# MotorCellOne.net
KiCad netlist of a schematic drawn in Altium Designer
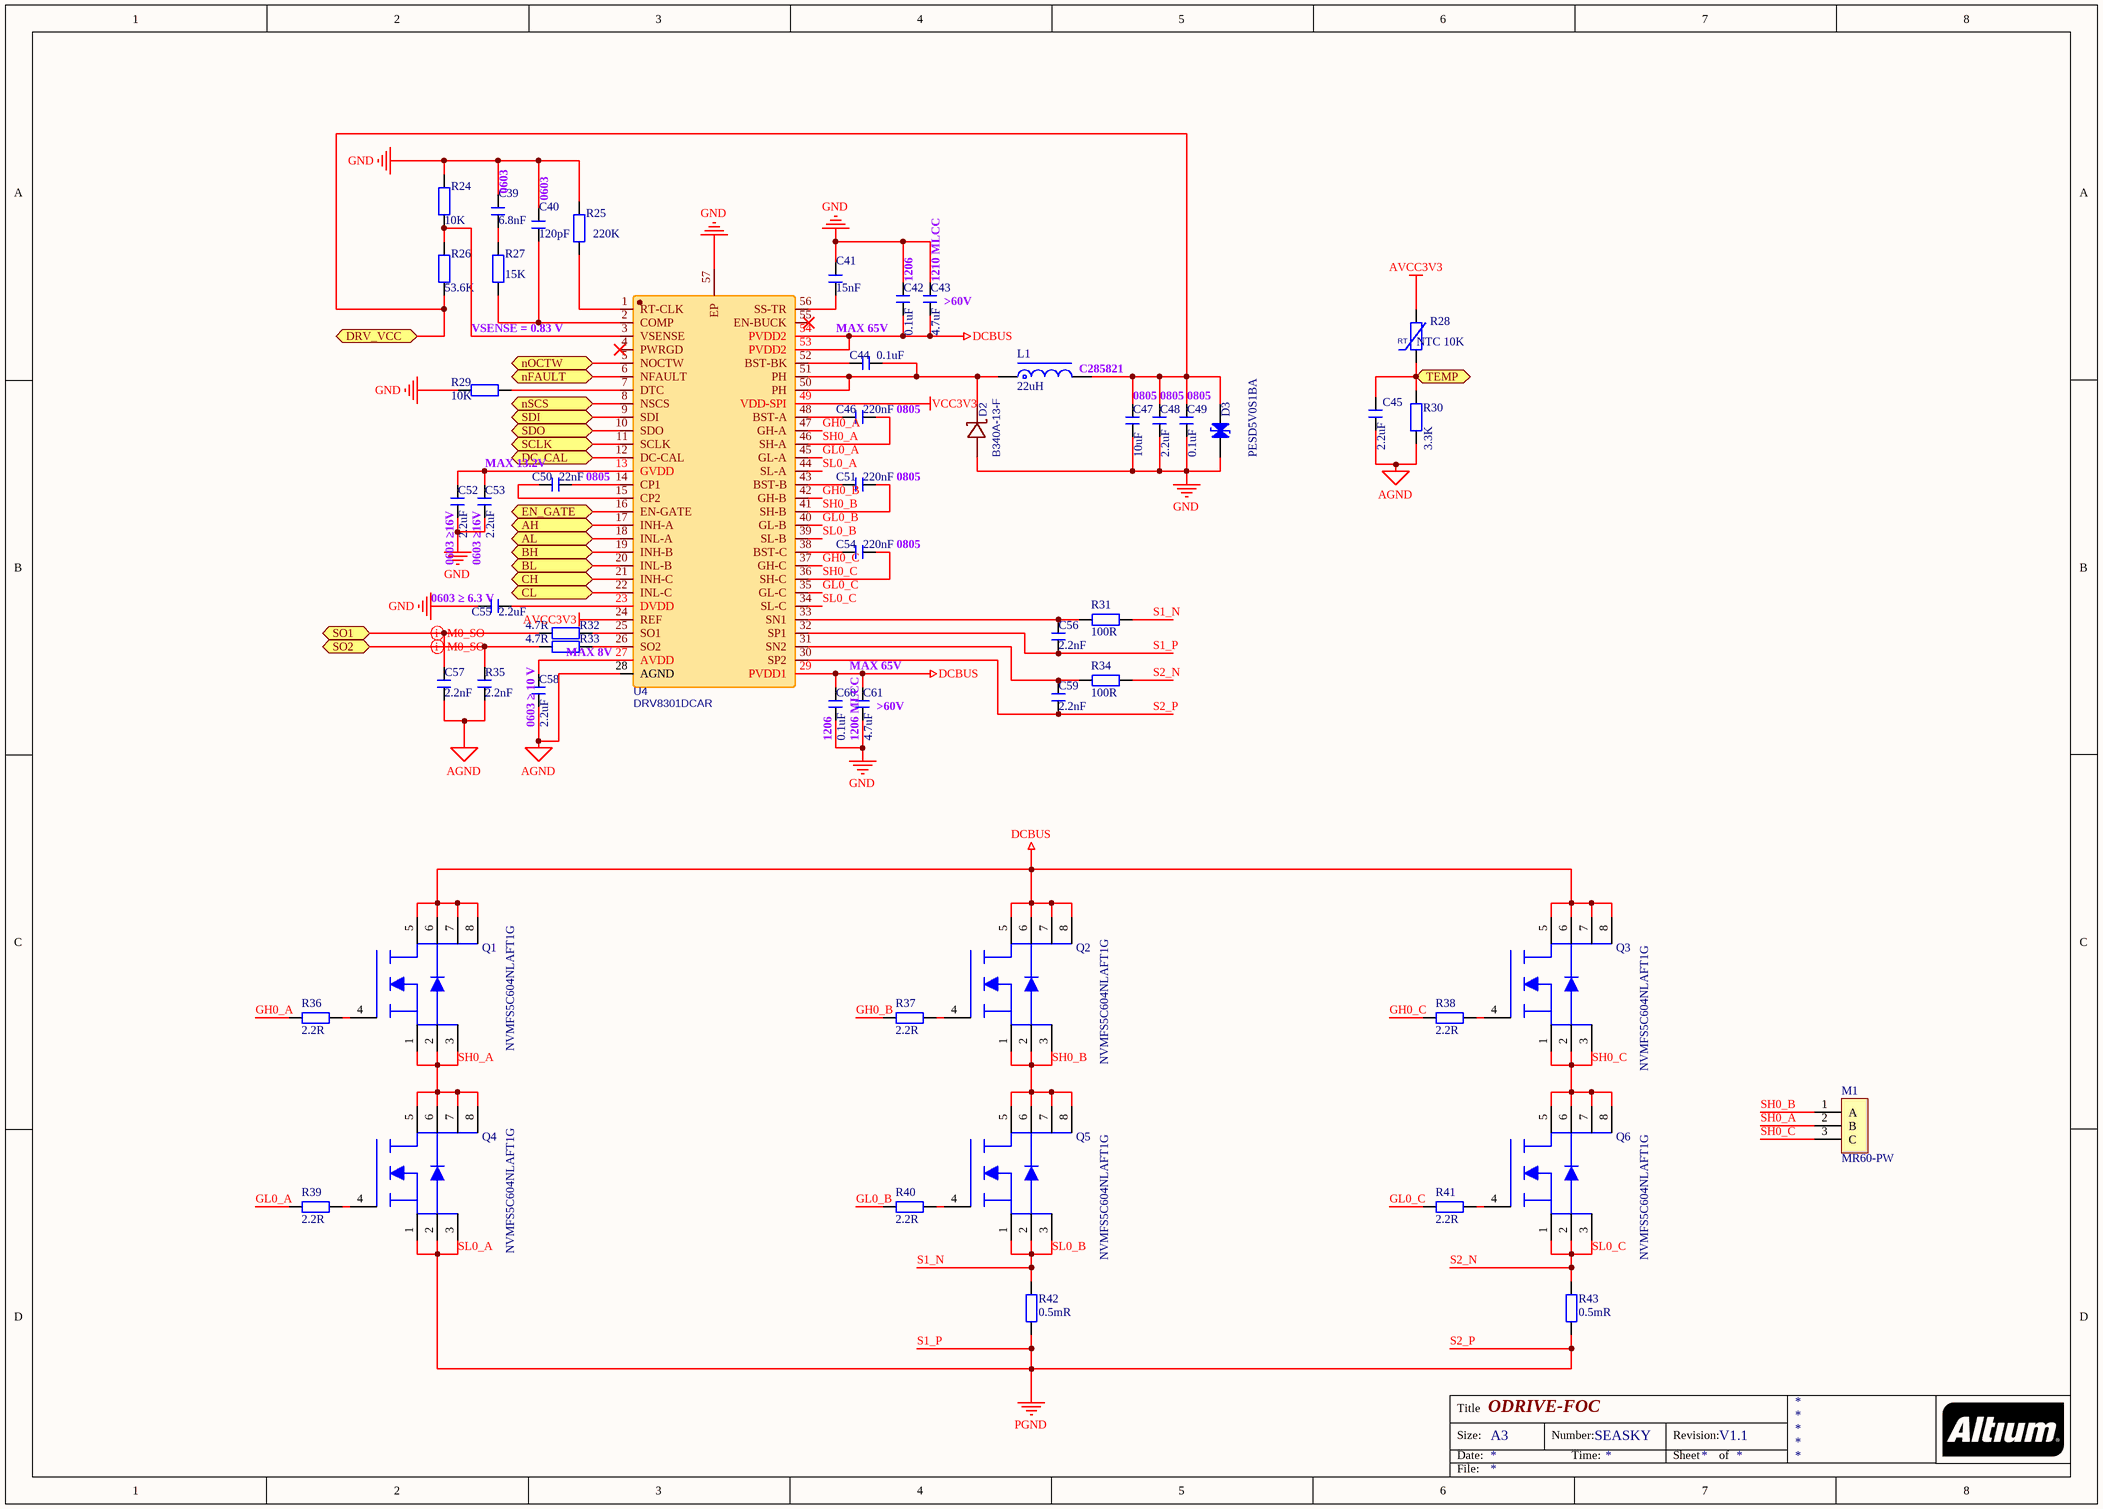
[diagram p0: MotorCellOne.SchDoc]

(export (version "E")
  (design (tool "Eeschema 10.0.6"))
  (components
    (comp (ref "C39")
      (value "6.8nF")
      (footprint "C 0603_L")
      (description "贴片电容")
      (libsource (lib "0.1 - 电阻-电容-电感") (part "C"))
    )
    (comp (ref "C40")
      (value "120pF")
      (footprint "C 0603_L")
      (description "贴片电容")
      (libsource (lib "0.1 - 电阻-电容-电感") (part "C"))
    )
    (comp (ref "C41")
      (value "15nF")
      (footprint "C 0603_L")
      (description "贴片电容")
      (libsource (lib "0.1 - 电阻-电容-电感") (part "C"))
    )
    (comp (ref "C42")
      (value "0.1uF")
      (footprint "C 1206_L")
      (description "贴片电容")
      (libsource (lib "0.1 - 电阻-电容-电感") (part "C"))
    )
    (comp (ref "C43")
      (value "4.7uF")
      (footprint "C 1210_L")
      (description "贴片电容")
      (libsource (lib "0.1 - 电阻-电容-电感") (part "C"))
    )
    (comp (ref "C44")
      (value "0.1uF")
      (footprint "C 0603_L")
      (description "贴片电容")
      (libsource (lib "0.1 - 电阻-电容-电感") (part "C"))
    )
    (comp (ref "C45")
      (value "2.2uF")
      (footprint "C 0603_L")
      (description "贴片电容")
      (libsource (lib "0.1 - 电阻-电容-电感") (part "C"))
    )
    (comp (ref "C46")
      (value "220nF")
      (footprint "C 0805_L")
      (description "贴片电容")
      (libsource (lib "0.1 - 电阻-电容-电感") (part "C"))
    )
    (comp (ref "C47")
      (value "10uF")
      (footprint "C 0805_L")
      (description "贴片电容")
      (libsource (lib "0.1 - 电阻-电容-电感") (part "C"))
    )
    (comp (ref "C48")
      (value "2.2uF")
      (footprint "C 0805_L")
      (description "贴片电容")
      (libsource (lib "0.1 - 电阻-电容-电感") (part "C"))
    )
    (comp (ref "C49")
      (value "0.1uF")
      (footprint "C 0805_L")
      (description "贴片电容")
      (libsource (lib "0.1 - 电阻-电容-电感") (part "C"))
    )
    (comp (ref "C50")
      (value "22nF")
      (footprint "C 0805_L")
      (description "贴片电容")
      (libsource (lib "0.1 - 电阻-电容-电感") (part "C"))
    )
    (comp (ref "C51")
      (value "220nF")
      (footprint "C 0805_L")
      (description "贴片电容")
      (libsource (lib "0.1 - 电阻-电容-电感") (part "C"))
    )
    (comp (ref "C52")
      (value "2.2uF")
      (footprint "C 0603_L")
      (description "贴片电容")
      (libsource (lib "0.1 - 电阻-电容-电感") (part "C"))
    )
    (comp (ref "C53")
      (value "2.2uF")
      (footprint "C 0603_L")
      (description "贴片电容")
      (libsource (lib "0.1 - 电阻-电容-电感") (part "C"))
    )
    (comp (ref "C54")
      (value "220nF")
      (footprint "C 0805_L")
      (description "贴片电容")
      (libsource (lib "0.1 - 电阻-电容-电感") (part "C"))
    )
    (comp (ref "C55")
      (value "2.2uF")
      (footprint "C 0603_L")
      (description "贴片电容")
      (libsource (lib "0.1 - 电阻-电容-电感") (part "C"))
    )
    (comp (ref "C56")
      (value "2.2nF")
      (footprint "C 0603_L")
      (description "贴片电容")
      (libsource (lib "0.1 - 电阻-电容-电感") (part "C"))
    )
    (comp (ref "C57")
      (value "2.2nF")
      (footprint "C 0603_L")
      (description "贴片电容")
      (libsource (lib "0.1 - 电阻-电容-电感") (part "C"))
    )
    (comp (ref "C58")
      (value "2.2uF")
      (footprint "C 0603_L")
      (description "贴片电容")
      (libsource (lib "0.1 - 电阻-电容-电感") (part "C"))
    )
    (comp (ref "C59")
      (value "2.2nF")
      (footprint "C 0603_L")
      (description "贴片电容")
      (libsource (lib "0.1 - 电阻-电容-电感") (part "C"))
    )
    (comp (ref "C60")
      (value "0.1uF")
      (footprint "C 1206_L")
      (description "贴片电容")
      (libsource (lib "0.1 - 电阻-电容-电感") (part "C"))
    )
    (comp (ref "C61")
      (value "4.7uF")
      (footprint "C 1210_L")
      (description "贴片电容")
      (libsource (lib "0.1 - 电阻-电容-电感") (part "C"))
    )
    (comp (ref "D2")
      (value "B340A-13-F")
      (footprint "SMA_L4.4-W2.6-LS5.0-RD")
      (fields (field (name "BOM_SUPPLIER PART") "C85098"))
      (libsource (lib "mx_pcb_library") (part "B340A-13-F"))
    )
    (comp (ref "D3")
      (value "PESD5V0S1BA")
      (footprint "SOD-323")
      (description "PESD5V0S1BA、ESD二极管、5V")
      (libsource (lib "0.2 -  二极管-整流桥") (part "PESD5V0S1BA"))
    )
    (comp (ref "L1")
      (value "22uH")
      (footprint "CD53")
      (description "CD系列贴片线绕功率电感")
      (libsource (lib "0.1 - 电阻-电容-电感") (part "L-SMD"))
    )
    (comp (ref "M1")
      (value "MR60-PW")
      (footprint "MR60-PW")
      (libsource (lib "mx_pcb_library") (part "MR60-PW"))
    )
    (comp (ref "Q1")
      (value "NVMFS5C604NLAFT1G")
      (footprint "PG-TDSON-8_L5.0-W6.0-P1.27-LS6.2-BL-EP")
      (libsource (lib "mx_pcb_library") (part "BSC037N08NS5ATMA1"))
    )
    (comp (ref "Q2")
      (value "NVMFS5C604NLAFT1G")
      (footprint "PG-TDSON-8_L5.0-W6.0-P1.27-LS6.2-BL-EP")
      (libsource (lib "mx_pcb_library") (part "BSC037N08NS5ATMA1"))
    )
    (comp (ref "Q3")
      (value "NVMFS5C604NLAFT1G")
      (footprint "PG-TDSON-8_L5.0-W6.0-P1.27-LS6.2-BL-EP")
      (libsource (lib "mx_pcb_library") (part "BSC037N08NS5ATMA1"))
    )
    (comp (ref "Q4")
      (value "NVMFS5C604NLAFT1G")
      (footprint "PG-TDSON-8_L5.0-W6.0-P1.27-LS6.2-BL-EP")
      (libsource (lib "mx_pcb_library") (part "BSC037N08NS5ATMA1"))
    )
    (comp (ref "Q5")
      (value "NVMFS5C604NLAFT1G")
      (footprint "PG-TDSON-8_L5.0-W6.0-P1.27-LS6.2-BL-EP")
      (libsource (lib "mx_pcb_library") (part "BSC037N08NS5ATMA1"))
    )
    (comp (ref "Q6")
      (value "NVMFS5C604NLAFT1G")
      (footprint "PG-TDSON-8_L5.0-W6.0-P1.27-LS6.2-BL-EP")
      (libsource (lib "mx_pcb_library") (part "BSC037N08NS5ATMA1"))
    )
    (comp (ref "R24")
      (value "10K")
      (footprint "R 0603_L")
      (description "贴片电阻")
      (libsource (lib "0.1 - 电阻-电容-电感") (part "R"))
    )
    (comp (ref "R25")
      (value "220K")
      (footprint "R 0603_L")
      (description "贴片电阻")
      (libsource (lib "0.1 - 电阻-电容-电感") (part "R"))
    )
    (comp (ref "R26")
      (value "53.6K")
      (footprint "R 0603_L")
      (description "贴片电阻")
      (libsource (lib "0.1 - 电阻-电容-电感") (part "R"))
    )
    (comp (ref "R27")
      (value "15K")
      (footprint "R 0603_L")
      (description "贴片电阻")
      (libsource (lib "0.1 - 电阻-电容-电感") (part "R"))
    )
    (comp (ref "R28")
      (value "NTC 10K")
      (footprint "R 0805-HP_L")
      (description "热敏电阻")
      (libsource (lib "0.1 - 电阻-电容-电感") (part "RT"))
    )
    (comp (ref "R29")
      (value "10K")
      (footprint "R 0603_L")
      (description "贴片电阻")
      (libsource (lib "0.1 - 电阻-电容-电感") (part "R"))
    )
    (comp (ref "R30")
      (value "3.3K")
      (footprint "R 0805_L")
      (description "贴片电阻")
      (libsource (lib "0.1 - 电阻-电容-电感") (part "R"))
    )
    (comp (ref "R31")
      (value "100R")
      (footprint "R 0603_L")
      (description "贴片电阻")
      (libsource (lib "0.1 - 电阻-电容-电感") (part "R"))
    )
    (comp (ref "R32")
      (value "4.7R")
      (footprint "R 0603_L")
      (description "贴片电阻")
      (libsource (lib "0.1 - 电阻-电容-电感") (part "R"))
    )
    (comp (ref "R33")
      (value "4.7R")
      (footprint "R 0603_L")
      (description "贴片电阻")
      (libsource (lib "0.1 - 电阻-电容-电感") (part "R"))
    )
    (comp (ref "R34")
      (value "100R")
      (footprint "R 0603_L")
      (description "贴片电阻")
      (libsource (lib "0.1 - 电阻-电容-电感") (part "R"))
    )
    (comp (ref "R35")
      (value "2.2nF")
      (footprint "C 0603_L")
      (description "贴片电容")
      (libsource (lib "0.1 - 电阻-电容-电感") (part "C"))
    )
    (comp (ref "R36")
      (value "2.2R")
      (footprint "R 0603_L")
      (description "贴片电阻")
      (libsource (lib "0.1 - 电阻-电容-电感") (part "R"))
    )
    (comp (ref "R37")
      (value "2.2R")
      (footprint "R 0603_L")
      (description "贴片电阻")
      (libsource (lib "0.1 - 电阻-电容-电感") (part "R"))
    )
    (comp (ref "R38")
      (value "2.2R")
      (footprint "R 0603_L")
      (description "贴片电阻")
      (libsource (lib "0.1 - 电阻-电容-电感") (part "R"))
    )
    (comp (ref "R39")
      (value "2.2R")
      (footprint "R 0603_L")
      (description "贴片电阻")
      (libsource (lib "0.1 - 电阻-电容-电感") (part "R"))
    )
    (comp (ref "R40")
      (value "2.2R")
      (footprint "R 0603_L")
      (description "贴片电阻")
      (libsource (lib "0.1 - 电阻-电容-电感") (part "R"))
    )
    (comp (ref "R41")
      (value "2.2R")
      (footprint "R 0603_L")
      (description "贴片电阻")
      (libsource (lib "0.1 - 电阻-电容-电感") (part "R"))
    )
    (comp (ref "R42")
      (value "0.5mR")
      (footprint "R3920")
      (description "精密贴片电阻")
      (libsource (lib "0.1 - 电阻-电容-电感") (part "R-Precision"))
    )
    (comp (ref "R43")
      (value "0.5mR")
      (footprint "R3920")
      (description "精密贴片电阻")
      (libsource (lib "0.1 - 电阻-电容-电感") (part "R-Precision"))
    )
    (comp (ref "U4")
      (value "DRV8301DCAR")
      (footprint "HTSSOP-56_L14.0-W6.0-P0.50-LS8.0-BL")
      (fields (field (name "BOM_SUPPLIER PART") "C98969") (field (name "CONTRIBUTOR") "LCSC"))
      (libsource (lib "mx_pcb_library") (part "DRV8301DCAR"))
    )
  )
  (nets
    (net (code "1") (name "/AH") (class "Default")
      (node (ref "U4") (pin "17") (pinfunction "INH-A_17") (pintype "passive"))
    )
    (net (code "2") (name "/AL") (class "Default")
      (node (ref "U4") (pin "18") (pinfunction "INL-A_18") (pintype "passive"))
    )
    (net (code "3") (name "/BH") (class "Default")
      (node (ref "U4") (pin "19") (pinfunction "INH-B_19") (pintype "passive"))
    )
    (net (code "4") (name "/BL") (class "Default")
      (node (ref "U4") (pin "20") (pinfunction "INL-B_20") (pintype "passive"))
    )
    (net (code "5") (name "/CH") (class "Default")
      (node (ref "U4") (pin "21") (pinfunction "INH-C_21") (pintype "passive"))
    )
    (net (code "6") (name "/CL") (class "Default")
      (node (ref "U4") (pin "22") (pinfunction "INL-C_22") (pintype "passive"))
    )
    (net (code "7") (name "/DC_CAL") (class "Default")
      (node (ref "U4") (pin "12") (pinfunction "DC-CAL_12") (pintype "passive"))
    )
    (net (code "8") (name "/DRV_VCC") (class "Default")
      (node (ref "C47") (pin "2") (pinfunction "2_2") (pintype "passive"))
      (node (ref "C48") (pin "2") (pinfunction "2_2") (pintype "passive"))
      (node (ref "C49") (pin "2") (pinfunction "2_2") (pintype "passive"))
      (node (ref "D3") (pin "1") (pinfunction "A_1") (pintype "passive"))
      (node (ref "L1") (pin "2") (pinfunction "2_2") (pintype "passive"))
      (node (ref "R26") (pin "1") (pinfunction "1_1") (pintype "passive"))
    )
    (net (code "9") (name "/EN_GATE") (class "Default")
      (node (ref "U4") (pin "16") (pinfunction "EN-GATE_16") (pintype "passive"))
    )
    (net (code "10") (name "/GH0_A") (class "Default")
      (node (ref "R36") (pin "1") (pinfunction "1_1") (pintype "passive"))
      (node (ref "U4") (pin "47") (pinfunction "GH-A_47") (pintype "passive"))
    )
    (net (code "11") (name "/GH0_B") (class "Default")
      (node (ref "R37") (pin "1") (pinfunction "1_1") (pintype "passive"))
      (node (ref "U4") (pin "42") (pinfunction "GH-B_42") (pintype "passive"))
    )
    (net (code "12") (name "/GH0_C") (class "Default")
      (node (ref "R38") (pin "1") (pinfunction "1_1") (pintype "passive"))
      (node (ref "U4") (pin "37") (pinfunction "GH-C_37") (pintype "passive"))
    )
    (net (code "13") (name "/GL0_A") (class "Default")
      (node (ref "R39") (pin "1") (pinfunction "1_1") (pintype "passive"))
      (node (ref "U4") (pin "45") (pinfunction "GL-A_45") (pintype "passive"))
    )
    (net (code "14") (name "/GL0_B") (class "Default")
      (node (ref "R40") (pin "1") (pinfunction "1_1") (pintype "passive"))
      (node (ref "U4") (pin "40") (pinfunction "GL-B_40") (pintype "passive"))
    )
    (net (code "15") (name "/GL0_C") (class "Default")
      (node (ref "R41") (pin "1") (pinfunction "1_1") (pintype "passive"))
      (node (ref "U4") (pin "35") (pinfunction "GL-C_35") (pintype "passive"))
    )
    (net (code "16") (name "/S1_N") (class "Default")
      (node (ref "Q5") (pin "1") (pinfunction "1_1") (pintype "passive"))
      (node (ref "Q5") (pin "2") (pinfunction "2_2") (pintype "passive"))
      (node (ref "Q5") (pin "3") (pinfunction "3_3") (pintype "passive"))
      (node (ref "R31") (pin "2") (pinfunction "2_2") (pintype "passive"))
      (node (ref "R42") (pin "2") (pinfunction "2_2") (pintype "passive"))
      (node (ref "U4") (pin "39") (pinfunction "SL-B_39") (pintype "passive"))
    )
    (net (code "17") (name "/S2_N") (class "Default")
      (node (ref "Q6") (pin "1") (pinfunction "1_1") (pintype "passive"))
      (node (ref "Q6") (pin "2") (pinfunction "2_2") (pintype "passive"))
      (node (ref "Q6") (pin "3") (pinfunction "3_3") (pintype "passive"))
      (node (ref "R34") (pin "2") (pinfunction "2_2") (pintype "passive"))
      (node (ref "R43") (pin "2") (pinfunction "2_2") (pintype "passive"))
      (node (ref "U4") (pin "34") (pinfunction "SL-C_34") (pintype "passive"))
    )
    (net (code "18") (name "/SCLK") (class "Default")
      (node (ref "U4") (pin "11") (pinfunction "SCLK_11") (pintype "passive"))
    )
    (net (code "19") (name "/SDI") (class "Default")
      (node (ref "U4") (pin "9") (pinfunction "SDI_9") (pintype "passive"))
    )
    (net (code "20") (name "/SDO") (class "Default")
      (node (ref "U4") (pin "10") (pinfunction "SDO_10") (pintype "passive"))
    )
    (net (code "21") (name "/SH0_A") (class "Default")
      (node (ref "C46") (pin "2") (pinfunction "2_2") (pintype "passive"))
      (node (ref "M1") (pin "2") (pinfunction "B_2") (pintype "passive"))
      (node (ref "Q1") (pin "1") (pinfunction "1_1") (pintype "passive"))
      (node (ref "Q1") (pin "2") (pinfunction "2_2") (pintype "passive"))
      (node (ref "Q1") (pin "3") (pinfunction "3_3") (pintype "passive"))
      (node (ref "Q4") (pin "5") (pinfunction "5_5") (pintype "passive"))
      (node (ref "Q4") (pin "6") (pinfunction "6_6") (pintype "passive"))
      (node (ref "Q4") (pin "7") (pinfunction "7_7") (pintype "passive"))
      (node (ref "Q4") (pin "8") (pinfunction "8_8") (pintype "passive"))
      (node (ref "U4") (pin "46") (pinfunction "SH-A_46") (pintype "passive"))
    )
    (net (code "22") (name "/SH0_B") (class "Default")
      (node (ref "C51") (pin "2") (pinfunction "2_2") (pintype "passive"))
      (node (ref "M1") (pin "1") (pinfunction "A_1") (pintype "passive"))
      (node (ref "Q2") (pin "1") (pinfunction "1_1") (pintype "passive"))
      (node (ref "Q2") (pin "2") (pinfunction "2_2") (pintype "passive"))
      (node (ref "Q2") (pin "3") (pinfunction "3_3") (pintype "passive"))
      (node (ref "Q5") (pin "5") (pinfunction "5_5") (pintype "passive"))
      (node (ref "Q5") (pin "6") (pinfunction "6_6") (pintype "passive"))
      (node (ref "Q5") (pin "7") (pinfunction "7_7") (pintype "passive"))
      (node (ref "Q5") (pin "8") (pinfunction "8_8") (pintype "passive"))
      (node (ref "U4") (pin "41") (pinfunction "SH-B_41") (pintype "passive"))
    )
    (net (code "23") (name "/SH0_C") (class "Default")
      (node (ref "C54") (pin "2") (pinfunction "2_2") (pintype "passive"))
      (node (ref "M1") (pin "3") (pinfunction "C_3") (pintype "passive"))
      (node (ref "Q3") (pin "1") (pinfunction "1_1") (pintype "passive"))
      (node (ref "Q3") (pin "2") (pinfunction "2_2") (pintype "passive"))
      (node (ref "Q3") (pin "3") (pinfunction "3_3") (pintype "passive"))
      (node (ref "Q6") (pin "5") (pinfunction "5_5") (pintype "passive"))
      (node (ref "Q6") (pin "6") (pinfunction "6_6") (pintype "passive"))
      (node (ref "Q6") (pin "7") (pinfunction "7_7") (pintype "passive"))
      (node (ref "Q6") (pin "8") (pinfunction "8_8") (pintype "passive"))
      (node (ref "U4") (pin "36") (pinfunction "SH-C_36") (pintype "passive"))
    )
    (net (code "24") (name "/SO1") (class "Default")
      (node (ref "C57") (pin "2") (pinfunction "2_2") (pintype "passive"))
      (node (ref "R32") (pin "1") (pinfunction "1_1") (pintype "passive"))
    )
    (net (code "25") (name "/SO2") (class "Default")
      (node (ref "R33") (pin "1") (pinfunction "1_1") (pintype "passive"))
      (node (ref "R35") (pin "2") (pinfunction "2_2") (pintype "passive"))
    )
    (net (code "26") (name "/TEMP") (class "Default")
      (node (ref "C45") (pin "1") (pinfunction "1_1") (pintype "passive"))
      (node (ref "R28") (pin "1") (pinfunction "1_1") (pintype "passive"))
      (node (ref "R30") (pin "2") (pinfunction "2_2") (pintype "passive"))
    )
    (net (code "27") (name "/nFAULT") (class "Default")
      (node (ref "U4") (pin "6") (pinfunction "NFAULT_6") (pintype "passive"))
    )
    (net (code "28") (name "/nOCTW") (class "Default")
      (node (ref "U4") (pin "5") (pinfunction "NOCTW_5") (pintype "passive"))
    )
    (net (code "29") (name "/nSCS") (class "Default")
      (node (ref "U4") (pin "8") (pinfunction "NSCS_8") (pintype "passive"))
    )
    (net (code "30") (name "AGND") (class "Default")
      (node (ref "C45") (pin "2") (pinfunction "2_2") (pintype "passive"))
      (node (ref "C57") (pin "1") (pinfunction "1_1") (pintype "passive"))
      (node (ref "C58") (pin "1") (pinfunction "1_1") (pintype "passive"))
      (node (ref "R30") (pin "1") (pinfunction "1_1") (pintype "passive"))
      (node (ref "R35") (pin "1") (pinfunction "1_1") (pintype "passive"))
      (node (ref "U4") (pin "28") (pinfunction "AGND_28") (pintype "passive"))
    )
    (net (code "31") (name "AVCC3V3") (class "Default")
      (node (ref "R28") (pin "2") (pinfunction "2_2") (pintype "passive"))
      (node (ref "U4") (pin "24") (pinfunction "REF_24") (pintype "passive"))
    )
    (net (code "32") (name "DCBUS") (class "Default")
      (node (ref "C42") (pin "1") (pinfunction "1_1") (pintype "passive"))
      (node (ref "C43") (pin "1") (pinfunction "1_1") (pintype "passive"))
      (node (ref "C60") (pin "2") (pinfunction "2_2") (pintype "passive"))
      (node (ref "C61") (pin "2") (pinfunction "2_2") (pintype "passive"))
      (node (ref "Q1") (pin "5") (pinfunction "5_5") (pintype "passive"))
      (node (ref "Q1") (pin "6") (pinfunction "6_6") (pintype "passive"))
      (node (ref "Q1") (pin "7") (pinfunction "7_7") (pintype "passive"))
      (node (ref "Q1") (pin "8") (pinfunction "8_8") (pintype "passive"))
      (node (ref "Q2") (pin "5") (pinfunction "5_5") (pintype "passive"))
      (node (ref "Q2") (pin "6") (pinfunction "6_6") (pintype "passive"))
      (node (ref "Q2") (pin "7") (pinfunction "7_7") (pintype "passive"))
      (node (ref "Q2") (pin "8") (pinfunction "8_8") (pintype "passive"))
      (node (ref "Q3") (pin "5") (pinfunction "5_5") (pintype "passive"))
      (node (ref "Q3") (pin "6") (pinfunction "6_6") (pintype "passive"))
      (node (ref "Q3") (pin "7") (pinfunction "7_7") (pintype "passive"))
      (node (ref "Q3") (pin "8") (pinfunction "8_8") (pintype "passive"))
      (node (ref "U4") (pin "29") (pinfunction "PVDD1_29") (pintype "passive"))
      (node (ref "U4") (pin "53") (pinfunction "PVDD2_53") (pintype "passive"))
      (node (ref "U4") (pin "54") (pinfunction "PVDD2_54") (pintype "passive"))
    )
    (net (code "33") (name "GND") (class "Default")
      (node (ref "C39") (pin "1") (pinfunction "1_1") (pintype "passive"))
      (node (ref "C40") (pin "1") (pinfunction "1_1") (pintype "passive"))
      (node (ref "C41") (pin "1") (pinfunction "1_1") (pintype "passive"))
      (node (ref "C42") (pin "2") (pinfunction "2_2") (pintype "passive"))
      (node (ref "C43") (pin "2") (pinfunction "2_2") (pintype "passive"))
      (node (ref "C47") (pin "1") (pinfunction "1_1") (pintype "passive"))
      (node (ref "C48") (pin "1") (pinfunction "1_1") (pintype "passive"))
      (node (ref "C49") (pin "1") (pinfunction "1_1") (pintype "passive"))
      (node (ref "C52") (pin "1") (pinfunction "1_1") (pintype "passive"))
      (node (ref "C53") (pin "1") (pinfunction "1_1") (pintype "passive"))
      (node (ref "C55") (pin "1") (pinfunction "1_1") (pintype "passive"))
      (node (ref "C60") (pin "1") (pinfunction "1_1") (pintype "passive"))
      (node (ref "C61") (pin "1") (pinfunction "1_1") (pintype "passive"))
      (node (ref "D2") (pin "2") (pinfunction "A_2") (pintype "passive"))
      (node (ref "D3") (pin "2") (pinfunction "K_2") (pintype "passive"))
      (node (ref "R24") (pin "2") (pinfunction "2_2") (pintype "passive"))
      (node (ref "R25") (pin "2") (pinfunction "2_2") (pintype "passive"))
      (node (ref "R29") (pin "2") (pinfunction "2_2") (pintype "passive"))
      (node (ref "U4") (pin "57") (pinfunction "EP_57") (pintype "passive"))
    )
    (net (code "34") (name "Net-(C39-Pad2)") (class "Default")
      (node (ref "C39") (pin "2") (pinfunction "2_2") (pintype "passive"))
      (node (ref "R27") (pin "2") (pinfunction "2_2") (pintype "passive"))
    )
    (net (code "35") (name "Net-(D2-K)") (class "Default")
      (node (ref "C44") (pin "1") (pinfunction "1_1") (pintype "passive"))
      (node (ref "D2") (pin "1") (pinfunction "K_1") (pintype "passive"))
      (node (ref "L1") (pin "1") (pinfunction "1_1") (pintype "passive"))
      (node (ref "U4") (pin "50") (pinfunction "PH_50") (pintype "passive"))
      (node (ref "U4") (pin "51") (pinfunction "PH_51") (pintype "passive"))
    )
    (net (code "36") (name "Net-(Q1-Pad4)") (class "Default")
      (node (ref "Q1") (pin "4") (pinfunction "4_4") (pintype "passive"))
      (node (ref "R36") (pin "2") (pinfunction "2_2") (pintype "passive"))
    )
    (net (code "37") (name "Net-(Q2-Pad4)") (class "Default")
      (node (ref "Q2") (pin "4") (pinfunction "4_4") (pintype "passive"))
      (node (ref "R37") (pin "2") (pinfunction "2_2") (pintype "passive"))
    )
    (net (code "38") (name "Net-(Q3-Pad4)") (class "Default")
      (node (ref "Q3") (pin "4") (pinfunction "4_4") (pintype "passive"))
      (node (ref "R38") (pin "2") (pinfunction "2_2") (pintype "passive"))
    )
    (net (code "39") (name "Net-(Q4-Pad4)") (class "Default")
      (node (ref "Q4") (pin "4") (pinfunction "4_4") (pintype "passive"))
      (node (ref "R39") (pin "2") (pinfunction "2_2") (pintype "passive"))
    )
    (net (code "40") (name "Net-(Q5-Pad4)") (class "Default")
      (node (ref "Q5") (pin "4") (pinfunction "4_4") (pintype "passive"))
      (node (ref "R40") (pin "2") (pinfunction "2_2") (pintype "passive"))
    )
    (net (code "41") (name "Net-(Q6-Pad4)") (class "Default")
      (node (ref "Q6") (pin "4") (pinfunction "4_4") (pintype "passive"))
      (node (ref "R41") (pin "2") (pinfunction "2_2") (pintype "passive"))
    )
    (net (code "42") (name "Net-(U4-AVDD)") (class "Default")
      (node (ref "C58") (pin "2") (pinfunction "2_2") (pintype "passive"))
      (node (ref "U4") (pin "27") (pinfunction "AVDD_27") (pintype "passive"))
    )
    (net (code "43") (name "Net-(U4-BST-A)") (class "Default")
      (node (ref "C46") (pin "1") (pinfunction "1_1") (pintype "passive"))
      (node (ref "U4") (pin "48") (pinfunction "BST-A_48") (pintype "passive"))
    )
    (net (code "44") (name "Net-(U4-BST-B)") (class "Default")
      (node (ref "C51") (pin "1") (pinfunction "1_1") (pintype "passive"))
      (node (ref "U4") (pin "43") (pinfunction "BST-B_43") (pintype "passive"))
    )
    (net (code "45") (name "Net-(U4-BST-BK)") (class "Default")
      (node (ref "C44") (pin "2") (pinfunction "2_2") (pintype "passive"))
      (node (ref "U4") (pin "52") (pinfunction "BST-BK_52") (pintype "passive"))
    )
    (net (code "46") (name "Net-(U4-BST-C)") (class "Default")
      (node (ref "C54") (pin "1") (pinfunction "1_1") (pintype "passive"))
      (node (ref "U4") (pin "38") (pinfunction "BST-C_38") (pintype "passive"))
    )
    (net (code "47") (name "Net-(U4-COMP)") (class "Default")
      (node (ref "C40") (pin "2") (pinfunction "2_2") (pintype "passive"))
      (node (ref "R27") (pin "1") (pinfunction "1_1") (pintype "passive"))
      (node (ref "U4") (pin "2") (pinfunction "COMP_2") (pintype "passive"))
    )
    (net (code "48") (name "Net-(U4-CP1)") (class "Default")
      (node (ref "C50") (pin "1") (pinfunction "1_1") (pintype "passive"))
      (node (ref "U4") (pin "14") (pinfunction "CP1_14") (pintype "passive"))
    )
    (net (code "49") (name "Net-(U4-CP2)") (class "Default")
      (node (ref "C50") (pin "2") (pinfunction "2_2") (pintype "passive"))
      (node (ref "U4") (pin "15") (pinfunction "CP2_15") (pintype "passive"))
    )
    (net (code "50") (name "Net-(U4-DTC)") (class "Default")
      (node (ref "R29") (pin "1") (pinfunction "1_1") (pintype "passive"))
      (node (ref "U4") (pin "7") (pinfunction "DTC_7") (pintype "passive"))
    )
    (net (code "51") (name "Net-(U4-DVDD)") (class "Default")
      (node (ref "C55") (pin "2") (pinfunction "2_2") (pintype "passive"))
      (node (ref "U4") (pin "23") (pinfunction "DVDD_23") (pintype "passive"))
    )
    (net (code "52") (name "Net-(U4-GVDD)") (class "Default")
      (node (ref "C52") (pin "2") (pinfunction "2_2") (pintype "passive"))
      (node (ref "C53") (pin "2") (pinfunction "2_2") (pintype "passive"))
      (node (ref "U4") (pin "13") (pinfunction "GVDD_13") (pintype "passive"))
    )
    (net (code "53") (name "Net-(U4-RT-CLK)") (class "Default")
      (node (ref "R25") (pin "1") (pinfunction "1_1") (pintype "passive"))
      (node (ref "U4") (pin "1") (pinfunction "RT-CLK_1") (pintype "passive"))
    )
    (net (code "54") (name "Net-(U4-SN1)") (class "Default")
      (node (ref "C56") (pin "2") (pinfunction "2_2") (pintype "passive"))
      (node (ref "R31") (pin "1") (pinfunction "1_1") (pintype "passive"))
      (node (ref "U4") (pin "33") (pinfunction "SN1_33") (pintype "passive"))
    )
    (net (code "55") (name "Net-(U4-SN2)") (class "Default")
      (node (ref "C59") (pin "2") (pinfunction "2_2") (pintype "passive"))
      (node (ref "R34") (pin "1") (pinfunction "1_1") (pintype "passive"))
      (node (ref "U4") (pin "31") (pinfunction "SN2_31") (pintype "passive"))
    )
    (net (code "56") (name "Net-(U4-SO1)") (class "Default")
      (node (ref "R32") (pin "2") (pinfunction "2_2") (pintype "passive"))
      (node (ref "U4") (pin "25") (pinfunction "SO1_25") (pintype "passive"))
    )
    (net (code "57") (name "Net-(U4-SO2)") (class "Default")
      (node (ref "R33") (pin "2") (pinfunction "2_2") (pintype "passive"))
      (node (ref "U4") (pin "26") (pinfunction "SO2_26") (pintype "passive"))
    )
    (net (code "58") (name "Net-(U4-SS-TR)") (class "Default")
      (node (ref "C41") (pin "2") (pinfunction "2_2") (pintype "passive"))
      (node (ref "U4") (pin "56") (pinfunction "SS-TR_56") (pintype "passive"))
    )
    (net (code "59") (name "Net-(U4-VSENSE)") (class "Default")
      (node (ref "R24") (pin "1") (pinfunction "1_1") (pintype "passive"))
      (node (ref "R26") (pin "2") (pinfunction "2_2") (pintype "passive"))
      (node (ref "U4") (pin "3") (pinfunction "VSENSE_3") (pintype "passive"))
    )
    (net (code "60") (name "PGND") (class "Default")
      (node (ref "C56") (pin "1") (pinfunction "1_1") (pintype "passive"))
      (node (ref "C59") (pin "1") (pinfunction "1_1") (pintype "passive"))
      (node (ref "Q4") (pin "1") (pinfunction "1_1") (pintype "passive"))
      (node (ref "Q4") (pin "2") (pinfunction "2_2") (pintype "passive"))
      (node (ref "Q4") (pin "3") (pinfunction "3_3") (pintype "passive"))
      (node (ref "R42") (pin "1") (pinfunction "1_1") (pintype "passive"))
      (node (ref "R43") (pin "1") (pinfunction "1_1") (pintype "passive"))
      (node (ref "U4") (pin "30") (pinfunction "SP2_30") (pintype "passive"))
      (node (ref "U4") (pin "32") (pinfunction "SP1_32") (pintype "passive"))
      (node (ref "U4") (pin "44") (pinfunction "SL-A_44") (pintype "passive"))
    )
    (net (code "61") (name "VCC3V3") (class "Default")
      (node (ref "U4") (pin "49") (pinfunction "VDD-SPI_49") (pintype "passive"))
    )
    (net (code "62") (name "unconnected-(U4-EN-BUCK-Pad55)") (class "Default")
      (node (ref "U4") (pin "55") (pinfunction "EN-BUCK_55") (pintype "passive+no_connect"))
    )
    (net (code "63") (name "unconnected-(U4-PWRGD-Pad4)") (class "Default")
      (node (ref "U4") (pin "4") (pinfunction "PWRGD_4") (pintype "passive+no_connect"))
    )
  )
)
